# potentiometer.net
KiCad netlist of a schematic drawn in EAGLE
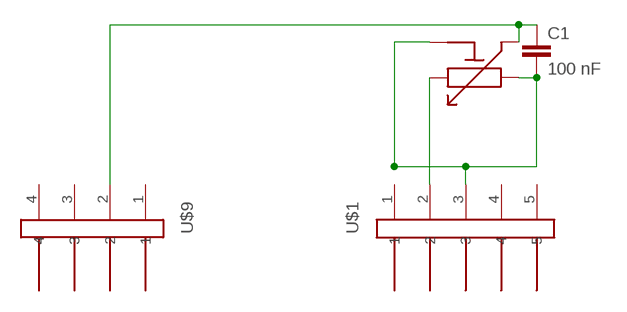
[diagram p0: schematic, sheet 1]

(export (version "E")
  (design (tool "Eeschema 10.0.6"))
  (components
    (comp (ref "C1")
      (value "100 nF")
      (footprint "eagle-import:C0805")
      (libsource (lib "eagle-import") (part "C-EUC0805"))
    )
    (comp (ref "U$1")
      (value "JUMPER5M")
      (footprint "eagle-import:JUMPER5M")
      (libsource (lib "eagle-import") (part "JUMPER5M"))
    )
    (comp (ref "U$2")
      (value "POTENTIOMETER-RK09")
      (footprint "eagle-import:POTENTIOMETER-RK09")
      (libsource (lib "eagle-import") (part "POTENTIOMETER-RK09"))
    )
    (comp (ref "U$9")
      (value "JUMPER4M")
      (footprint "eagle-import:JUMPER4M")
      (libsource (lib "eagle-import") (part "JUMPER4M"))
    )
  )
  (nets
    (net (code "1") (name "Net-(C1-Pad1)") (class "Default")
      (node (ref "C1") (pin "1") (pinfunction "1_1") (pintype "passive"))
      (node (ref "U$2") (pin "2") (pinfunction "2_2") (pintype "bidirectional"))
      (node (ref "U$9") (pin "2") (pinfunction "2_2") (pintype "bidirectional"))
    )
    (net (code "2") (name "Net-(C1-Pad2)") (class "Default")
      (node (ref "C1") (pin "2") (pinfunction "2_2") (pintype "passive"))
      (node (ref "U$1") (pin "3") (pinfunction "3_3") (pintype "bidirectional"))
      (node (ref "U$2") (pin "1") (pinfunction "1_1") (pintype "bidirectional"))
      (node (ref "U$2") (pin "GND1") (pinfunction "GND_GND1") (pintype "power_in"))
      (node (ref "U$2") (pin "GND2") (pinfunction "GND_GND2") (pintype "power_in"))
    )
    (net (code "3") (name "Net-(U$1-Pad2)") (class "Default")
      (node (ref "U$1") (pin "2") (pinfunction "2_2") (pintype "bidirectional"))
      (node (ref "U$2") (pin "3") (pinfunction "3_3") (pintype "bidirectional"))
    )
    (net (code "4") (name "unconnected-(U$1-Pad1)") (class "Default")
      (node (ref "U$1") (pin "1") (pinfunction "1_1") (pintype "bidirectional"))
    )
    (net (code "5") (name "unconnected-(U$1-Pad4)") (class "Default")
      (node (ref "U$1") (pin "4") (pinfunction "4_4") (pintype "bidirectional"))
    )
    (net (code "6") (name "unconnected-(U$1-Pad5)") (class "Default")
      (node (ref "U$1") (pin "5") (pinfunction "5_5") (pintype "bidirectional"))
    )
    (net (code "7") (name "unconnected-(U$9-Pad1)") (class "Default")
      (node (ref "U$9") (pin "1") (pinfunction "1_1") (pintype "bidirectional"))
    )
    (net (code "8") (name "unconnected-(U$9-Pad3)") (class "Default")
      (node (ref "U$9") (pin "3") (pinfunction "3_3") (pintype "bidirectional"))
    )
    (net (code "9") (name "unconnected-(U$9-Pad4)") (class "Default")
      (node (ref "U$9") (pin "4") (pinfunction "4_4") (pintype "bidirectional"))
    )
  )
)
